# puente_H_rama_2.net
KiCad netlist of a schematic drawn in Altium Designer
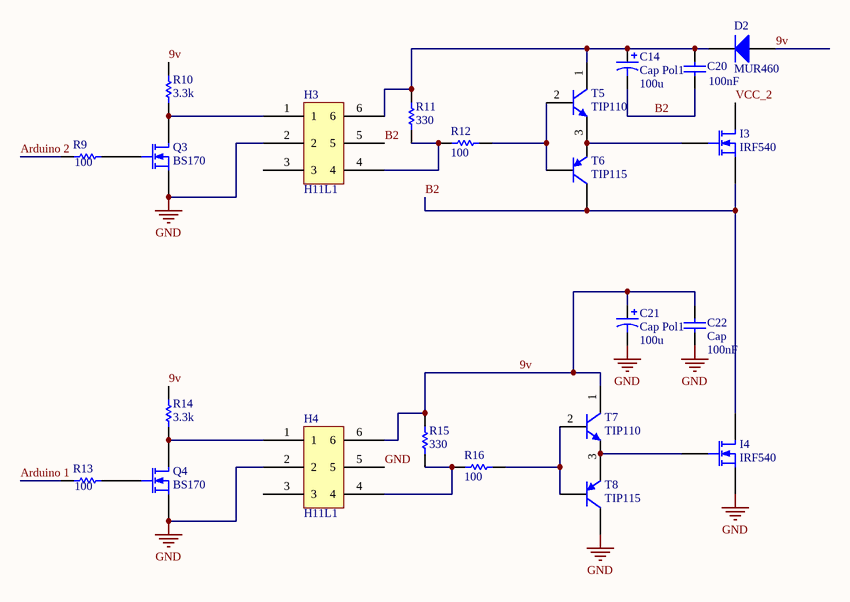
[diagram p0: puente H rama 2.SchDoc]

(export (version "E")
  (design (tool "Eeschema 10.0.6"))
  (components
    (comp (ref "C14")
      (value "Cap Pol1")
      (footprint "A")
      (description "Polarized Capacitor (Radial)")
      (fields (field (name "ALTIUM_VALUE") "100u") (field (name "PUBLISHER") "Altium Limited"))
      (libsource (lib "Miscellaneous Devices") (part "Cap Pol1"))
    )
    (comp (ref "C20")
      (value "100nF")
      (footprint "C1206")
      (description "Capacitor")
      (fields (field (name "Comment") "Cap") (field (name "PUBLISHER") "Altium Limited"))
      (libsource (lib "Miscellaneous Devices") (part "Cap"))
    )
    (comp (ref "C21")
      (value "Cap Pol1")
      (footprint "A")
      (description "Polarized Capacitor (Radial)")
      (fields (field (name "ALTIUM_VALUE") "100u") (field (name "PUBLISHER") "Altium Limited"))
      (libsource (lib "Miscellaneous Devices") (part "Cap Pol1"))
    )
    (comp (ref "C22")
      (value "Cap")
      (footprint "C1206")
      (description "Capacitor")
      (fields (field (name "ALTIUM_VALUE") "100nF") (field (name "PUBLISHER") "Altium Limited"))
      (libsource (lib "Miscellaneous Devices") (part "Cap"))
    )
    (comp (ref "D2")
      (value "MUR460")
      (footprint "DO-201AD")
      (description "Default Diode")
      (fields (field (name "PUBLISHER") "Altium Limited"))
      (libsource (lib "Miscellaneous Devices") (part "Diode"))
    )
    (comp (ref "H3") (value "H11L1") (footprint "DIP-6") (libsource (lib "H11L1") (part "H11L1")))
    (comp (ref "H4") (value "H11L1") (footprint "DIP-6") (libsource (lib "H11L1") (part "H11L1")))
    (comp (ref "I3")
      (value "IRF540")
      (footprint "TO-220AB")
      (description "N-Channel MOSFET")
      (fields (field (name "PUBLISHER") "Altium Limited"))
      (libsource (lib "Miscellaneous Devices") (part "MOSFET-N"))
    )
    (comp (ref "I4")
      (value "IRF540")
      (footprint "TO-220-AB")
      (description "N-Channel MOSFET")
      (fields (field (name "PUBLISHER") "Altium Limited"))
      (libsource (lib "Miscellaneous Devices") (part "MOSFET-N"))
    )
    (comp (ref "Q3")
      (value "BS170")
      (footprint "E3")
      (description "N-Channel MOSFET")
      (fields (field (name "PUBLISHER") "Altium Limited"))
      (libsource (lib "Miscellaneous Devices") (part "MOSFET-N"))
    )
    (comp (ref "Q4")
      (value "BS170")
      (footprint "E3")
      (description "N-Channel MOSFET")
      (fields (field (name "PUBLISHER") "Altium Limited"))
      (libsource (lib "Miscellaneous Devices") (part "MOSFET-N"))
    )
    (comp (ref "R9")
      (value "100")
      (footprint "3216[1206]")
      (description "Resistor")
      (fields (field (name "Comment") "Res1") (field (name "PUBLISHER") "Altium Limited"))
      (libsource (lib "Miscellaneous Devices") (part "Res1"))
    )
    (comp (ref "R10")
      (value "3.3k")
      (footprint "3216[1206]")
      (description "Resistor")
      (fields (field (name "Comment") "Res1") (field (name "PUBLISHER") "Altium Limited"))
      (libsource (lib "Miscellaneous Devices") (part "Res1"))
    )
    (comp (ref "R11")
      (value "330")
      (footprint "3216[1206]")
      (description "Resistor")
      (fields (field (name "Comment") "Res1") (field (name "PUBLISHER") "Altium Limited"))
      (libsource (lib "Miscellaneous Devices") (part "Res1"))
    )
    (comp (ref "R12")
      (value "100")
      (footprint "3216[1206]")
      (description "Resistor")
      (fields (field (name "Comment") "Res1") (field (name "PUBLISHER") "Altium Limited"))
      (libsource (lib "Miscellaneous Devices") (part "Res1"))
    )
    (comp (ref "R13")
      (value "100")
      (footprint "3216[1206]")
      (description "Resistor")
      (fields (field (name "Comment") "Res1") (field (name "PUBLISHER") "Altium Limited"))
      (libsource (lib "Miscellaneous Devices") (part "Res1"))
    )
    (comp (ref "R14")
      (value "3.3k")
      (footprint "3216[1206]")
      (description "Resistor")
      (fields (field (name "Comment") "Res1") (field (name "PUBLISHER") "Altium Limited"))
      (libsource (lib "Miscellaneous Devices") (part "Res1"))
    )
    (comp (ref "R15")
      (value "330")
      (footprint "3216[1206]")
      (description "Resistor")
      (fields (field (name "Comment") "Res1") (field (name "PUBLISHER") "Altium Limited"))
      (libsource (lib "Miscellaneous Devices") (part "Res1"))
    )
    (comp (ref "R16")
      (value "100")
      (footprint "3216[1206]")
      (description "Resistor")
      (fields (field (name "Comment") "Res1") (field (name "PUBLISHER") "Altium Limited"))
      (libsource (lib "Miscellaneous Devices") (part "Res1"))
    )
    (comp (ref "T5")
      (value "TIP110")
      (footprint "TO-220-AB")
      (description "NPN Bipolar Transistor")
      (fields (field (name "PUBLISHER") "Altium Limited"))
      (libsource (lib "Miscellaneous Devices") (part "NPN"))
    )
    (comp (ref "T6")
      (value "TIP115")
      (footprint "TO-220-AB")
      (description "PNP Bipolar Transistor")
      (fields (field (name "PUBLISHER") "Altium Limited"))
      (libsource (lib "Miscellaneous Devices") (part "PNP"))
    )
    (comp (ref "T7")
      (value "TIP110")
      (footprint "TO-220-AB")
      (description "NPN Bipolar Transistor")
      (fields (field (name "PUBLISHER") "Altium Limited"))
      (libsource (lib "Miscellaneous Devices") (part "NPN"))
    )
    (comp (ref "T8")
      (value "TIP115")
      (footprint "TO-220-AB")
      (description "PNP Bipolar Transistor")
      (fields (field (name "PUBLISHER") "Altium Limited"))
      (libsource (lib "Miscellaneous Devices") (part "PNP"))
    )
  )
  (nets
    (net (code "1") (name "/9v") (class "Default")
      (node (ref "C21") (pin "1") (pinfunction "1_1") (pintype "passive"))
      (node (ref "C22") (pin "2") (pinfunction "2_2") (pintype "passive"))
      (node (ref "D2") (pin "1") (pinfunction "A_1") (pintype "passive"))
      (node (ref "H4") (pin "6") (pinfunction "6_6") (pintype "passive"))
      (node (ref "R10") (pin "2") (pinfunction "2_2") (pintype "passive"))
      (node (ref "R14") (pin "2") (pinfunction "2_2") (pintype "passive"))
      (node (ref "R15") (pin "2") (pinfunction "2_2") (pintype "passive"))
      (node (ref "T7") (pin "1") (pinfunction "C_1") (pintype "passive"))
    )
    (net (code "2") (name "/Arduino 1") (class "Default")
      (node (ref "R13") (pin "1") (pinfunction "1_1") (pintype "passive"))
    )
    (net (code "3") (name "/Arduino 2") (class "Default")
      (node (ref "R9") (pin "1") (pinfunction "1_1") (pintype "passive"))
    )
    (net (code "4") (name "/B2") (class "Default")
      (node (ref "C14") (pin "2") (pinfunction "2_2") (pintype "passive"))
      (node (ref "C20") (pin "1") (pinfunction "1_1") (pintype "passive"))
      (node (ref "H3") (pin "5") (pinfunction "5_5") (pintype "passive"))
      (node (ref "I3") (pin "3") (pinfunction "S_3") (pintype "passive"))
      (node (ref "I4") (pin "1") (pinfunction "D_1") (pintype "passive"))
      (node (ref "T6") (pin "1") (pinfunction "C_1") (pintype "passive"))
    )
    (net (code "5") (name "/VCC_2") (class "Default")
      (node (ref "I3") (pin "1") (pinfunction "D_1") (pintype "passive"))
    )
    (net (code "6") (name "GND") (class "Default")
      (node (ref "C21") (pin "2") (pinfunction "2_2") (pintype "passive"))
      (node (ref "C22") (pin "1") (pinfunction "1_1") (pintype "passive"))
      (node (ref "H3") (pin "2") (pinfunction "2_2") (pintype "passive"))
      (node (ref "H4") (pin "2") (pinfunction "2_2") (pintype "passive"))
      (node (ref "H4") (pin "5") (pinfunction "5_5") (pintype "passive"))
      (node (ref "I4") (pin "3") (pinfunction "S_3") (pintype "passive"))
      (node (ref "Q3") (pin "3") (pinfunction "S_3") (pintype "passive"))
      (node (ref "Q4") (pin "3") (pinfunction "S_3") (pintype "passive"))
      (node (ref "T8") (pin "1") (pinfunction "C_1") (pintype "passive"))
    )
    (net (code "7") (name "Net-(D2-K)") (class "Default")
      (node (ref "C14") (pin "1") (pinfunction "1_1") (pintype "passive"))
      (node (ref "C20") (pin "2") (pinfunction "2_2") (pintype "passive"))
      (node (ref "D2") (pin "2") (pinfunction "K_2") (pintype "passive"))
      (node (ref "H3") (pin "6") (pinfunction "6_6") (pintype "passive"))
      (node (ref "R11") (pin "2") (pinfunction "2_2") (pintype "passive"))
      (node (ref "T5") (pin "1") (pinfunction "C_1") (pintype "passive"))
    )
    (net (code "8") (name "Net-(H3-Pad4)") (class "Default")
      (node (ref "H3") (pin "4") (pinfunction "4_4") (pintype "passive"))
      (node (ref "R11") (pin "1") (pinfunction "1_1") (pintype "passive"))
      (node (ref "R12") (pin "2") (pinfunction "2_2") (pintype "passive"))
    )
    (net (code "9") (name "Net-(H4-Pad4)") (class "Default")
      (node (ref "H4") (pin "4") (pinfunction "4_4") (pintype "passive"))
      (node (ref "R15") (pin "1") (pinfunction "1_1") (pintype "passive"))
      (node (ref "R16") (pin "2") (pinfunction "2_2") (pintype "passive"))
    )
    (net (code "10") (name "Net-(I3-G)") (class "Default")
      (node (ref "I3") (pin "2") (pinfunction "G_2") (pintype "passive"))
      (node (ref "T5") (pin "3") (pinfunction "E_3") (pintype "passive"))
      (node (ref "T6") (pin "3") (pinfunction "E_3") (pintype "passive"))
    )
    (net (code "11") (name "Net-(I4-G)") (class "Default")
      (node (ref "I4") (pin "2") (pinfunction "G_2") (pintype "passive"))
      (node (ref "T7") (pin "3") (pinfunction "E_3") (pintype "passive"))
      (node (ref "T8") (pin "3") (pinfunction "E_3") (pintype "passive"))
    )
    (net (code "12") (name "Net-(Q3-D)") (class "Default")
      (node (ref "H3") (pin "1") (pinfunction "1_1") (pintype "passive"))
      (node (ref "Q3") (pin "1") (pinfunction "D_1") (pintype "passive"))
      (node (ref "R10") (pin "1") (pinfunction "1_1") (pintype "passive"))
    )
    (net (code "13") (name "Net-(Q3-G)") (class "Default")
      (node (ref "Q3") (pin "2") (pinfunction "G_2") (pintype "passive"))
      (node (ref "R9") (pin "2") (pinfunction "2_2") (pintype "passive"))
    )
    (net (code "14") (name "Net-(Q4-D)") (class "Default")
      (node (ref "H4") (pin "1") (pinfunction "1_1") (pintype "passive"))
      (node (ref "Q4") (pin "1") (pinfunction "D_1") (pintype "passive"))
      (node (ref "R14") (pin "1") (pinfunction "1_1") (pintype "passive"))
    )
    (net (code "15") (name "Net-(Q4-G)") (class "Default")
      (node (ref "Q4") (pin "2") (pinfunction "G_2") (pintype "passive"))
      (node (ref "R13") (pin "2") (pinfunction "2_2") (pintype "passive"))
    )
    (net (code "16") (name "Net-(T5-B)") (class "Default")
      (node (ref "R12") (pin "1") (pinfunction "1_1") (pintype "passive"))
      (node (ref "T5") (pin "2") (pinfunction "B_2") (pintype "passive"))
      (node (ref "T6") (pin "2") (pinfunction "B_2") (pintype "passive"))
    )
    (net (code "17") (name "Net-(T7-B)") (class "Default")
      (node (ref "R16") (pin "1") (pinfunction "1_1") (pintype "passive"))
      (node (ref "T7") (pin "2") (pinfunction "B_2") (pintype "passive"))
      (node (ref "T8") (pin "2") (pinfunction "B_2") (pintype "passive"))
    )
    (net (code "18") (name "unconnected-(H3-Pad3)") (class "Default")
      (node (ref "H3") (pin "3") (pinfunction "3_3") (pintype "passive"))
    )
    (net (code "19") (name "unconnected-(H4-Pad3)") (class "Default")
      (node (ref "H4") (pin "3") (pinfunction "3_3") (pintype "passive"))
    )
  )
)
